# CONTROLLER_SECTION.net
KiCad netlist of a schematic drawn in Altium Designer
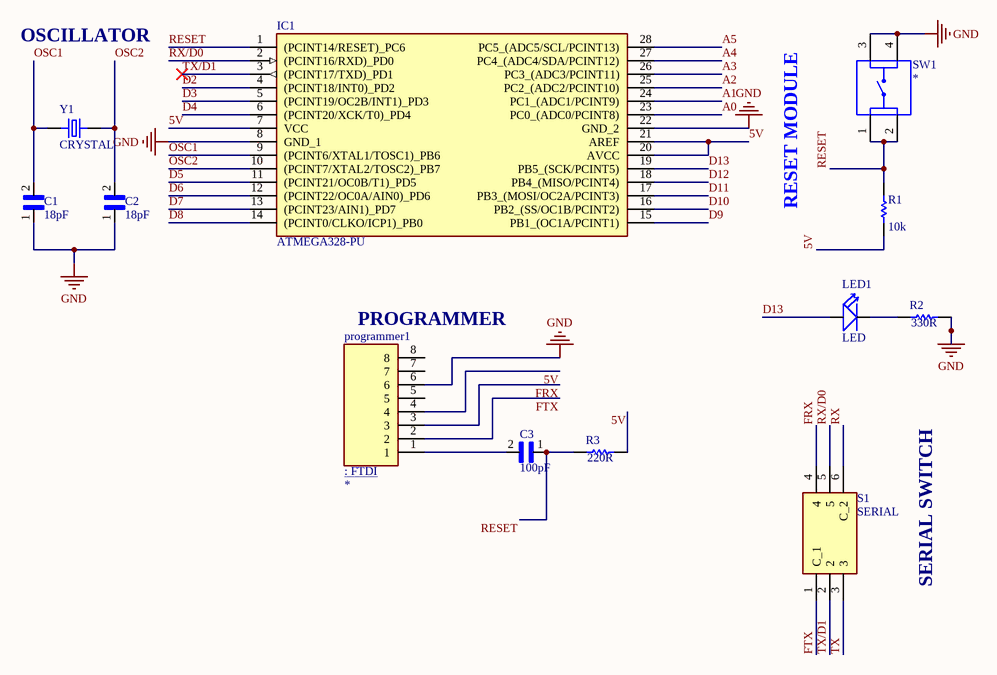
[diagram p0: CONTROLLER SECTION.SchDoc]

(export (version "E")
  (design (tool "Eeschema 10.0.6"))
  (components
    (comp (ref "C1")
      (value "18pF")
      (footprint "CAP_DE21XSA100KN3AY02F")
      (fields (field (name "MP") "DE21XSA100KN3AY02F"))
      (libsource (lib "") (part "DE21XSA100KN3AY02F_1"))
    )
    (comp (ref "C2")
      (value "18pF")
      (footprint "CAP_DE21XSA100KN3AY02F")
      (fields (field (name "MP") "DE21XSA100KN3AY02F"))
      (libsource (lib "") (part "DE21XSA100KN3AY02F_1"))
    )
    (comp (ref "C3")
      (value "100pF")
      (footprint "CAP_DE21XSA100KN3AY02F")
      (fields (field (name "MP") "DE21XSA100KN3AY02F"))
      (libsource (lib "nonpolar capacitor round 3D") (part "DE21XSA100KN3AY02F"))
    )
    (comp (ref "IC1")
      (value "ATMEGA328-PU")
      (footprint "SamacSys:DIP1016W53P254L3468H457Q28N")
      (description "Integrated Circuit")
      (fields (field (name "MOUSER PART NUMBER") "556-ATMEGA328-PU"))
      (libsource (lib "AVR328p with 3d model") (part "ATMEGA328-PU"))
    )
    (comp (ref "LED1")
      (value "LED")
      (footprint "LED2-2.54-D10MM")
      (description "DIP LED Green-Vaporous Green-10mm")
      (fields (field (name "MF") "Chengguangxing") (field (name "MP") "G1004DC"))
      (libsource (lib "LED 3D") (part "DIP-LED-GREEN-VAPOROUS-GREEN-10MM(2P-D10MM)"))
    )
    (comp (ref "programmer1")
      (value "87247-8")
      (footprint "TE_87247-8")
      (description "Connector Header Through Hole 8 position 0.156 (3.96mm)")
      (fields
        (field (name "MF") "TE Connectivity")
        (field (name "ALTIUM_UNNAMED_1") "FTDI")
        (field (name "COMMENT_1") "*")
      )
      (libsource (lib "8pin male header 3D") (part "87247-8"))
    )
    (comp (ref "R1")
      (value "10k")
      (footprint "AXIAL-0.5")
      (description "Semiconductor Resistor")
      (fields (field (name "PUBLISHER") "Altium Limited"))
      (libsource (lib "Miscellaneous Devices") (part "Res Semi"))
    )
    (comp (ref "R2")
      (value "330R")
      (footprint "AXIAL-0.5")
      (description "Semiconductor Resistor")
      (fields (field (name "PUBLISHER") "Altium Limited"))
      (libsource (lib "Miscellaneous Devices") (part "Res Semi"))
    )
    (comp (ref "R3")
      (value "220R")
      (footprint "AXIAL-0.5")
      (description "Semiconductor Resistor")
      (fields (field (name "PUBLISHER") "Altium Limited"))
      (libsource (lib "Miscellaneous Devices") (part "Res Semi"))
    )
    (comp (ref "S1")
      (value "SERIAL")
      (footprint "SamacSys:MPSA22E080150")
      (description "Switch")
      (fields (field (name "MANUFACTURER_PART_NUMBER") "MPSA-22E08-0150"))
      (libsource (lib "6pin push button") (part "MPSA-22E08-0150"))
    )
    (comp (ref "SW1")
      (value "1825910-6")
      (footprint "SW_1825910-6-4")
      (description "Switch Push Button OFF _ON_ SPST Round Button 0.05A 24VDC Momentary Contact PC Pins Thru-Hole")
      (fields
        (field (name "MF") "TE Connectivity")
        (field (name "DIGI-KEY_PART_NUMBER") "450-1650-ND")
        (field (name "COMMENT_1") "*")
      )
      (libsource (lib "pushbutton") (part "1825910-6"))
    )
    (comp (ref "Y1")
      (value "CRYSTAL")
      (footprint "XTAL_ECS-60-20-4VX")
      (description "20MHz Â±30ppm Crystal 20pF 40 Ohms HC-49/US")
      (fields (field (name "MF") "ECS International") (field (name "MP") "ECS-200-20-4VX"))
      (libsource (lib "CRYSTAL16") (part "ECS-200-20-4VX"))
    )
  )
  (nets
    (net (code "1") (name "/5V") (class "Default")
      (node (ref "IC1") (pin "20") (pinfunction "AVCC_20") (pintype "power_in"))
      (node (ref "IC1") (pin "21") (pinfunction "AREF_21") (pintype "passive"))
      (node (ref "IC1") (pin "7") (pinfunction "VCC_7") (pintype "power_in"))
      (node (ref "R1") (pin "1") (pinfunction "1_1") (pintype "passive"))
      (node (ref "R3") (pin "1") (pinfunction "1_1") (pintype "passive"))
      (node (ref "programmer1") (pin "4") (pinfunction "4_4") (pintype "passive"))
    )
    (net (code "2") (name "/A0") (class "Default")
      (node (ref "IC1") (pin "23") (pinfunction "PC0_(ADC0/PCINT8)_23") (pintype "passive"))
    )
    (net (code "3") (name "/A1") (class "Default")
      (node (ref "IC1") (pin "24") (pinfunction "PC1_(ADC1/PCINT9)_24") (pintype "passive"))
    )
    (net (code "4") (name "/A2") (class "Default")
      (node (ref "IC1") (pin "25") (pinfunction "PC2_(ADC2/PCINT10)_25") (pintype "passive"))
    )
    (net (code "5") (name "/A3") (class "Default")
      (node (ref "IC1") (pin "26") (pinfunction "PC3_(ADC3/PCINT11)_26") (pintype "passive"))
    )
    (net (code "6") (name "/A4") (class "Default")
      (node (ref "IC1") (pin "27") (pinfunction "PC4_(ADC4/SDA/PCINT12)_27") (pintype "passive"))
    )
    (net (code "7") (name "/A5") (class "Default")
      (node (ref "IC1") (pin "28") (pinfunction "PC5_(ADC5/SCL/PCINT13)_28") (pintype "passive"))
    )
    (net (code "8") (name "/D2") (class "Default")
      (node (ref "IC1") (pin "4") (pinfunction "(PCINT18/INT0)_PD2_4") (pintype "passive"))
    )
    (net (code "9") (name "/D3") (class "Default")
      (node (ref "IC1") (pin "5") (pinfunction "(PCINT19/OC2B/INT1)_PD3_5") (pintype "passive"))
    )
    (net (code "10") (name "/D4") (class "Default")
      (node (ref "IC1") (pin "6") (pinfunction "(PCINT20/XCK/T0)_PD4_6") (pintype "passive"))
    )
    (net (code "11") (name "/D5") (class "Default")
      (node (ref "IC1") (pin "11") (pinfunction "(PCINT21/OC0B/T1)_PD5_11") (pintype "passive"))
    )
    (net (code "12") (name "/D6") (class "Default")
      (node (ref "IC1") (pin "12") (pinfunction "(PCINT22/OC0A/AIN0)_PD6_12") (pintype "passive"))
    )
    (net (code "13") (name "/D7") (class "Default")
      (node (ref "IC1") (pin "13") (pinfunction "(PCINT23/AIN1)_PD7_13") (pintype "passive"))
    )
    (net (code "14") (name "/D8") (class "Default")
      (node (ref "IC1") (pin "14") (pinfunction "(PCINT0/CLKO/ICP1)_PB0_14") (pintype "passive"))
    )
    (net (code "15") (name "/D9") (class "Default")
      (node (ref "IC1") (pin "15") (pinfunction "PB1_(OC1A/PCINT1)_15") (pintype "passive"))
    )
    (net (code "16") (name "/D10") (class "Default")
      (node (ref "IC1") (pin "16") (pinfunction "PB2_(SS/OC1B/PCINT2)_16") (pintype "passive"))
    )
    (net (code "17") (name "/D11") (class "Default")
      (node (ref "IC1") (pin "17") (pinfunction "PB3_(MOSI/OC2A/PCINT3)_17") (pintype "passive"))
    )
    (net (code "18") (name "/D12") (class "Default")
      (node (ref "IC1") (pin "18") (pinfunction "PB4_(MISO/PCINT4)_18") (pintype "passive"))
    )
    (net (code "19") (name "/D13") (class "Default")
      (node (ref "IC1") (pin "19") (pinfunction "PB5_(SCK/PCINT5)_19") (pintype "passive"))
      (node (ref "LED1") (pin "POS") (pinfunction "POS_POS") (pintype "passive"))
    )
    (net (code "20") (name "/FRX") (class "Default")
      (node (ref "S1") (pin "4") (pinfunction "4_4") (pintype "passive"))
      (node (ref "programmer1") (pin "3") (pinfunction "3_3") (pintype "passive"))
    )
    (net (code "21") (name "/FTX") (class "Default")
      (node (ref "S1") (pin "1") (pinfunction "C_1_1") (pintype "passive"))
      (node (ref "programmer1") (pin "2") (pinfunction "2_2") (pintype "passive"))
    )
    (net (code "22") (name "/OSC1") (class "Default")
      (node (ref "C1") (pin "2") (pinfunction "2_2") (pintype "passive"))
      (node (ref "IC1") (pin "9") (pinfunction "(PCINT6/XTAL1/TOSC1)_PB6_9") (pintype "passive"))
      (node (ref "Y1") (pin "1") (pinfunction "1_1") (pintype "passive"))
    )
    (net (code "23") (name "/OSC2") (class "Default")
      (node (ref "C2") (pin "2") (pinfunction "2_2") (pintype "passive"))
      (node (ref "IC1") (pin "10") (pinfunction "(PCINT7/XTAL2/TOSC2)_PB7_10") (pintype "passive"))
      (node (ref "Y1") (pin "2") (pinfunction "2_2") (pintype "passive"))
    )
    (net (code "24") (name "/RESET") (class "Default")
      (node (ref "C3") (pin "1") (pinfunction "1_1") (pintype "passive"))
      (node (ref "IC1") (pin "1") (pinfunction "(PCINT14/RESET)_PC6_1") (pintype "passive"))
      (node (ref "R1") (pin "2") (pinfunction "2_2") (pintype "passive"))
      (node (ref "R3") (pin "2") (pinfunction "2_2") (pintype "passive"))
      (node (ref "SW1") (pin "1") (pinfunction "1_1") (pintype "passive"))
      (node (ref "SW1") (pin "2") (pinfunction "2_2") (pintype "passive"))
    )
    (net (code "25") (name "/RX") (class "Default")
      (node (ref "S1") (pin "6") (pinfunction "C_2_6") (pintype "passive"))
    )
    (net (code "26") (name "/RX{slash}D0") (class "Default")
      (node (ref "IC1") (pin "2") (pinfunction "(PCINT16/RXD)_PD0_2") (pintype "input"))
      (node (ref "S1") (pin "5") (pinfunction "5_5") (pintype "passive"))
    )
    (net (code "27") (name "/TX") (class "Default")
      (node (ref "S1") (pin "3") (pinfunction "3_3") (pintype "passive"))
    )
    (net (code "28") (name "/TX{slash}D1") (class "Default")
      (node (ref "IC1") (pin "3") (pinfunction "(PCINT17/TXD)_PD1_3") (pintype "output"))
      (node (ref "S1") (pin "2") (pinfunction "2_2") (pintype "passive"))
    )
    (net (code "29") (name "GND") (class "Default")
      (node (ref "C1") (pin "1") (pinfunction "1_1") (pintype "passive"))
      (node (ref "C2") (pin "1") (pinfunction "1_1") (pintype "passive"))
      (node (ref "IC1") (pin "22") (pinfunction "GND_2_22") (pintype "power_in"))
      (node (ref "IC1") (pin "8") (pinfunction "GND_1_8") (pintype "power_in"))
      (node (ref "R2") (pin "2") (pinfunction "2_2") (pintype "passive"))
      (node (ref "SW1") (pin "3") (pinfunction "3_3") (pintype "passive"))
      (node (ref "SW1") (pin "4") (pinfunction "4_4") (pintype "passive"))
      (node (ref "programmer1") (pin "6") (pinfunction "6_6") (pintype "passive"))
    )
    (net (code "30") (name "Net-(C3-Pad2)") (class "Default")
      (node (ref "C3") (pin "2") (pinfunction "2_2") (pintype "passive"))
      (node (ref "programmer1") (pin "1") (pinfunction "1_1") (pintype "passive"))
    )
    (net (code "31") (name "Net-(LED1-PadNEG)") (class "Default")
      (node (ref "LED1") (pin "NEG") (pinfunction "NEG_NEG") (pintype "passive"))
      (node (ref "R2") (pin "1") (pinfunction "1_1") (pintype "passive"))
    )
    (net (code "32") (name "unconnected-(programmer1-Pad5)") (class "Default")
      (node (ref "programmer1") (pin "5") (pinfunction "5_5") (pintype "passive"))
    )
    (net (code "33") (name "unconnected-(programmer1-Pad7)") (class "Default")
      (node (ref "programmer1") (pin "7") (pinfunction "7_7") (pintype "passive"))
    )
    (net (code "34") (name "unconnected-(programmer1-Pad8)") (class "Default")
      (node (ref "programmer1") (pin "8") (pinfunction "8_8") (pintype "passive"))
    )
  )
)
